# Sheet1.net
KiCad netlist of a schematic drawn in Altium Designer
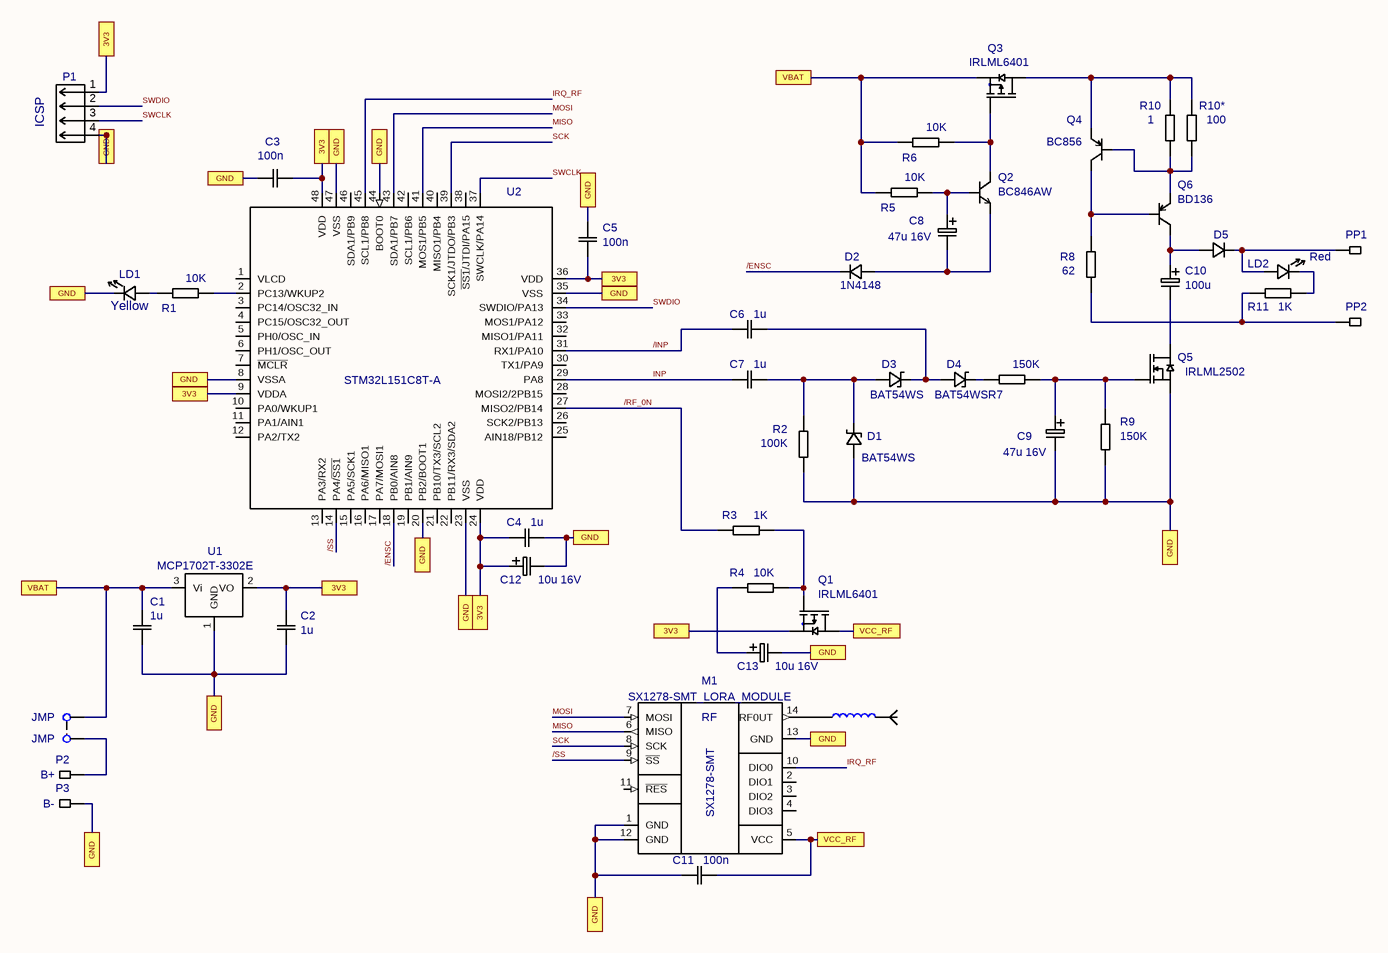
[diagram p0: Sheet1.SCHDOC]

(export (version "E")
  (design (tool "Eeschema 10.0.6"))
  (components
    (comp (ref "C1")
      (value "1u")
      (footprint "C0805")
      (description "CAP_SMD_0805")
      (libsource (lib "*") (part "CAP_SMD_0805"))
    )
    (comp (ref "C2")
      (value "1u")
      (footprint "C0805")
      (description "CAP_SMD_0805")
      (libsource (lib "*") (part "CAP_SMD_0805"))
    )
    (comp (ref "C3")
      (value "100n")
      (footprint "C0805")
      (description "CAP_SMD_0805")
      (libsource (lib "") (part "CAP_SMD_0805_2"))
    )
    (comp (ref "C4")
      (value "1u")
      (footprint "C0805")
      (description "CAP_SMD_0805")
      (libsource (lib "") (part "CAP_SMD_0805_2"))
    )
    (comp (ref "C5")
      (value "100n")
      (footprint "C0805")
      (description "CAP_SMD_0805")
      (libsource (lib "*") (part "CAP_SMD_0805"))
    )
    (comp (ref "C6")
      (value "1u")
      (footprint "C0805")
      (description "CAP_SMD_0805")
      (libsource (lib "") (part "CAP_SMD_0805_2"))
    )
    (comp (ref "C7")
      (value "1u")
      (footprint "C0805")
      (description "CAP_SMD_0805")
      (libsource (lib "") (part "CAP_SMD_0805_1"))
    )
    (comp (ref "C8")
      (value "47u 16V")
      (footprint "ECAP-SD-D5L11")
      (description "ECAP-RD-D5L11")
      (libsource (lib "*") (part "ECAP-RD-D5L11"))
    )
    (comp (ref "C9")
      (value "47u 16V")
      (footprint "ECAP-SD-D5L11")
      (description "ECAP-RD-D5L11")
      (libsource (lib "*") (part "ECAP-RD-D5L11"))
    )
    (comp (ref "C10")
      (value "100u")
      (footprint "ECAP-SD-D6.3L11")
      (description "ECAP-RD-D6.3L11")
      (libsource (lib "*") (part "ECAP-RD-D6.3L11"))
    )
    (comp (ref "C11")
      (value "100n")
      (footprint "C0805")
      (description "CAP_SMD_0805")
      (libsource (lib "") (part "CAP_SMD_0805_1"))
    )
    (comp (ref "C12")
      (value "10u 16V")
      (footprint "ECAP-SD-D5L11")
      (description "ECAP-RD-D5L11")
      (libsource (lib "*") (part "ECAP-RD-D5L11"))
    )
    (comp (ref "C13")
      (value "10u 16V")
      (footprint "ECAP-SD-D5L11")
      (description "ECAP-RD-D5L11")
      (libsource (lib "*") (part "ECAP-RD-D5L11"))
    )
    (comp (ref "D1") (value "BAT54WS") (footprint "SOD323") (libsource (lib "*") (part "BAT54WS")))
    (comp (ref "D2") (value "1N4148") (footprint "SOD80") (libsource (lib "*") (part "1N4148")))
    (comp (ref "D3") (value "BAT54WS") (footprint "SOD323") (libsource (lib "*") (part "BAT54WS")))
    (comp (ref "D4") (value "BAT54WS") (footprint "SOD323") (libsource (lib "*") (part "BAT54WS")))
    (comp (ref "D5") (value "1N4007-A7") (footprint "SOD-123FL") (libsource (lib "*") (part "1N4007-A7")))
    (comp (ref "LD1")
      (value "Yellow")
      (footprint "LED_SMD_0805")
      (description "Yellow LED. 2.6Vf")
      (fields (field (name "Comment") "FYLS-0805BYC LED"))
      (libsource (lib "*") (part "FYLS-0805BYC LED"))
    )
    (comp (ref "LD2")
      (value "Red")
      (footprint "LED_SMD_0805")
      (description "Ultra Red. Vf-1.85V(2.2V max)")
      (fields (field (name "Comment") "FYLS-0805URC LED"))
      (libsource (lib "*") (part "FYLS-0805URC LED"))
    )
    (comp (ref "M1")
      (value "SX1278-SMT_LORA_MODULE")
      (footprint "SX1278-SMT_MODULE")
      (libsource (lib "*") (part "SX1278-SMT_LORA_MODULE"))
    )
    (comp (ref "P1")
      (value "ICSP")
      (footprint "PLS-04SMD")
      (description "PLS-04SMD")
      (libsource (lib "*") (part "PLS-04SMD"))
    )
    (comp (ref "P2")
      (value "B+")
      (footprint "PAD_RRX60Y120D0T")
      (description "PAD_RRX60Y120D0T")
      (libsource (lib "*") (part "PAD_RRX60Y120D0T"))
    )
    (comp (ref "P3")
      (value "B-")
      (footprint "PAD_RRX60Y120D0T")
      (description "PAD_RRX60Y120D0T")
      (libsource (lib "*") (part "PAD_RRX60Y120D0T"))
    )
    (comp (ref "PP1")
      (value "PAD_RRX60Y120D0T")
      (footprint "PAD_RRX60Y120D0T")
      (libsource (lib "*") (part "PAD_RRX60Y120D0T"))
    )
    (comp (ref "PP2")
      (value "PAD_RRX60Y120D0T")
      (footprint "PAD_RRX60Y120D0T")
      (libsource (lib "*") (part "PAD_RRX60Y120D0T"))
    )
    (comp (ref "PP3")
      (value "JMP")
      (footprint "PAD_RX60Y60D38A")
      (description "PAD_RX60Y60D38A")
      (libsource (lib "*") (part "PAD_RX60Y60D38A"))
    )
    (comp (ref "PP4")
      (value "JMP")
      (footprint "PAD_RX60Y60D38A")
      (description "PAD_RX60Y60D38A")
      (libsource (lib "*") (part "PAD_RX60Y60D38A"))
    )
    (comp (ref "Q1") (value "IRLML6401") (footprint "SOT23") (libsource (lib "*") (part "IRLML6401")))
    (comp (ref "Q2") (value "BC846AW") (footprint "SOT23") (libsource (lib "*") (part "BC846AW")))
    (comp (ref "Q3") (value "IRLML6401") (footprint "SOT23") (libsource (lib "") (part "IRLML6401_1")))
    (comp (ref "Q4") (value "BC856") (footprint "SOT23") (libsource (lib "*") (part "BC856")))
    (comp (ref "Q5") (value "IRLML2502") (footprint "SOT23") (libsource (lib "*") (part "IRLML2502")))
    (comp (ref "Q6") (value "BD136") (footprint "TO225 VH") (libsource (lib "*") (part "BD136")))
    (comp (ref "R1")
      (value "10K")
      (footprint "R0805")
      (description "RES_SMD_0805")
      (libsource (lib "*") (part "RES_SMD_0805"))
    )
    (comp (ref "R2")
      (value "100K")
      (footprint "R0805")
      (description "RES_SMD_0805")
      (libsource (lib "*") (part "RES_SMD_0805"))
    )
    (comp (ref "R3")
      (value "1K")
      (footprint "R0805")
      (description "RES_SMD_0805")
      (libsource (lib "*") (part "RES_SMD_0805"))
    )
    (comp (ref "R4")
      (value "10K")
      (footprint "R0805")
      (description "RES_SMD_0805")
      (libsource (lib "*") (part "RES_SMD_0805"))
    )
    (comp (ref "R5")
      (value "10K")
      (footprint "R0805")
      (description "RES_SMD_0805")
      (libsource (lib "*") (part "RES_SMD_0805"))
    )
    (comp (ref "R6")
      (value "10K")
      (footprint "R0805")
      (description "RES_SMD_0805")
      (libsource (lib "*") (part "RES_SMD_0805"))
    )
    (comp (ref "R7")
      (value "150K")
      (footprint "R0805")
      (description "RES_SMD_0805")
      (libsource (lib "*") (part "RES_SMD_0805"))
    )
    (comp (ref "R8")
      (value "62")
      (footprint "R0805")
      (description "RES_SMD_0805")
      (libsource (lib "*") (part "RES_SMD_0805"))
    )
    (comp (ref "R9")
      (value "150K")
      (footprint "R0805")
      (description "RES_SMD_0805")
      (libsource (lib "*") (part "RES_SMD_0805"))
    )
    (comp (ref "R10")
      (value "1")
      (footprint "R0805")
      (description "RES_SMD_0805")
      (libsource (lib "*") (part "RES_SMD_0805"))
    )
    (comp (ref "R10*")
      (value "100")
      (footprint "R0805")
      (description "RES_SMD_0805")
      (libsource (lib "*") (part "RES_SMD_0805"))
    )
    (comp (ref "R11")
      (value "1K")
      (footprint "R0805")
      (description "RES_SMD_0805")
      (libsource (lib "*") (part "RES_SMD_0805"))
    )
    (comp (ref "U1")
      (value "MCP1702T-3302E")
      (footprint "SOT23A")
      (libsource (lib "*") (part "MCP1702T-3302E"))
    )
    (comp (ref "U2")
      (value "STM32L151C8T-A")
      (footprint "LQFP48 7X7")
      (libsource (lib "*") (part "STM32L151C8T-A"))
    )
  )
  (nets
    (net (code "1") (name "/3V3") (class "Default")
      (node (ref "C12") (pin "1") (pintype "passive"))
      (node (ref "C2") (pin "2") (pinfunction "B_2") (pintype "passive"))
      (node (ref "C3") (pin "1") (pinfunction "A_1") (pintype "passive"))
      (node (ref "C4") (pin "2") (pinfunction "B_2") (pintype "passive"))
      (node (ref "C5") (pin "1") (pinfunction "A_1") (pintype "passive"))
      (node (ref "P1") (pin "1") (pintype "passive"))
      (node (ref "Q1") (pin "2") (pinfunction "S_2") (pintype "passive"))
      (node (ref "U1") (pin "2") (pinfunction "VO_2") (pintype "passive"))
      (node (ref "U2") (pin "24") (pinfunction "VDD_24") (pintype "power_in"))
      (node (ref "U2") (pin "36") (pinfunction "VDD_36") (pintype "power_in"))
      (node (ref "U2") (pin "48") (pinfunction "VDD_48") (pintype "power_in"))
      (node (ref "U2") (pin "9") (pinfunction "VDDA_9") (pintype "power_in"))
    )
    (net (code "2") (name "/GND") (class "Default")
      (node (ref "C1") (pin "1") (pinfunction "A_1") (pintype "passive"))
      (node (ref "C11") (pin "1") (pinfunction "A_1") (pintype "passive"))
      (node (ref "C12") (pin "2") (pintype "passive"))
      (node (ref "C13") (pin "2") (pintype "passive"))
      (node (ref "C2") (pin "1") (pinfunction "A_1") (pintype "passive"))
      (node (ref "C3") (pin "2") (pinfunction "B_2") (pintype "passive"))
      (node (ref "C4") (pin "1") (pinfunction "A_1") (pintype "passive"))
      (node (ref "C5") (pin "2") (pinfunction "B_2") (pintype "passive"))
      (node (ref "C9") (pin "2") (pintype "passive"))
      (node (ref "D1") (pin "1") (pintype "passive"))
      (node (ref "LD1") (pin "K") (pinfunction "K_K") (pintype "passive"))
      (node (ref "M1") (pin "1") (pinfunction "GND_1") (pintype "power_in"))
      (node (ref "M1") (pin "12") (pinfunction "GND_12") (pintype "power_in"))
      (node (ref "M1") (pin "13") (pinfunction "GND_13") (pintype "power_in"))
      (node (ref "P1") (pin "4") (pintype "passive"))
      (node (ref "P3") (pin "1") (pintype "passive"))
      (node (ref "Q5") (pin "2") (pinfunction "S_2") (pintype "passive"))
      (node (ref "R2") (pin "2") (pintype "passive"))
      (node (ref "R9") (pin "2") (pintype "passive"))
      (node (ref "U1") (pin "1") (pinfunction "GND_1") (pintype "passive"))
      (node (ref "U2") (pin "20") (pinfunction "PB2/BOOT1_20") (pintype "bidirectional"))
      (node (ref "U2") (pin "23") (pinfunction "VSS_23") (pintype "power_in"))
      (node (ref "U2") (pin "35") (pinfunction "VSS_35") (pintype "power_in"))
      (node (ref "U2") (pin "44") (pinfunction "BOOT0_44") (pintype "input"))
      (node (ref "U2") (pin "47") (pinfunction "VSS_47") (pintype "power_in"))
      (node (ref "U2") (pin "8") (pinfunction "VSSA_8") (pintype "power_in"))
    )
    (net (code "3") (name "/INP") (class "Default")
      (node (ref "C7") (pin "1") (pinfunction "A_1") (pintype "passive"))
      (node (ref "U2") (pin "29") (pinfunction "PA8_29") (pintype "bidirectional"))
    )
    (net (code "4") (name "/IRQ_RF") (class "Default")
      (node (ref "M1") (pin "10") (pinfunction "DIO0_10") (pintype "bidirectional"))
      (node (ref "U2") (pin "45") (pinfunction "SCL1/PB8_45") (pintype "bidirectional"))
    )
    (net (code "5") (name "/MISO") (class "Default")
      (node (ref "M1") (pin "6") (pinfunction "MISO_6") (pintype "output"))
      (node (ref "U2") (pin "41") (pinfunction "MOS1/PB5_41") (pintype "bidirectional"))
    )
    (net (code "6") (name "/MOSI") (class "Default")
      (node (ref "M1") (pin "7") (pinfunction "MOSI_7") (pintype "input"))
      (node (ref "U2") (pin "43") (pinfunction "SDA1/PB7_43") (pintype "bidirectional"))
    )
    (net (code "7") (name "/SCK") (class "Default")
      (node (ref "M1") (pin "8") (pinfunction "SCK_8") (pintype "input"))
      (node (ref "U2") (pin "39") (pinfunction "SCK1/JTDO/PB3_39") (pintype "bidirectional"))
    )
    (net (code "8") (name "/SWCLK") (class "Default")
      (node (ref "P1") (pin "3") (pintype "passive"))
      (node (ref "U2") (pin "37") (pinfunction "SWCLK/PA14_37") (pintype "bidirectional"))
    )
    (net (code "9") (name "/SWDIO") (class "Default")
      (node (ref "P1") (pin "2") (pintype "passive"))
      (node (ref "U2") (pin "34") (pinfunction "SWDIO/PA13_34") (pintype "bidirectional"))
    )
    (net (code "10") (name "/VBAT") (class "Default")
      (node (ref "C1") (pin "2") (pinfunction "B_2") (pintype "passive"))
      (node (ref "PP4") (pin "1") (pintype "passive"))
      (node (ref "Q3") (pin "2") (pinfunction "S_2") (pintype "passive"))
      (node (ref "R5") (pin "2") (pintype "passive"))
      (node (ref "R6") (pin "2") (pintype "passive"))
      (node (ref "U1") (pin "3") (pinfunction "Vi_3") (pintype "passive"))
    )
    (net (code "11") (name "/VCC_RF") (class "Default")
      (node (ref "C11") (pin "2") (pinfunction "B_2") (pintype "passive"))
      (node (ref "M1") (pin "5") (pinfunction "VCC_5") (pintype "power_in"))
      (node (ref "Q1") (pin "3") (pinfunction "D_3") (pintype "passive"))
    )
    (net (code "12") (name "/{slash}ENSC") (class "Default")
      (node (ref "D2") (pin "K") (pinfunction "K_K") (pintype "passive"))
      (node (ref "U2") (pin "18") (pinfunction "PB0/AIN8_18") (pintype "bidirectional"))
    )
    (net (code "13") (name "/{slash}INP") (class "Default")
      (node (ref "C6") (pin "2") (pinfunction "B_2") (pintype "passive"))
      (node (ref "U2") (pin "31") (pinfunction "RX1/PA10_31") (pintype "bidirectional"))
    )
    (net (code "14") (name "/{slash}RF_0N") (class "Default")
      (node (ref "R3") (pin "2") (pintype "passive"))
      (node (ref "U2") (pin "27") (pinfunction "MISO2/PB14_27") (pintype "bidirectional"))
    )
    (net (code "15") (name "/{slash}SS") (class "Default")
      (node (ref "M1") (pin "9") (pinfunction "~{SS}_9") (pintype "input"))
      (node (ref "U2") (pin "14") (pinfunction "PA4/~{SS1}_14") (pintype "bidirectional"))
    )
    (net (code "16") (name "Net-(C6-A)") (class "Default")
      (node (ref "C6") (pin "1") (pinfunction "A_1") (pintype "passive"))
      (node (ref "D3") (pin "2") (pintype "passive"))
      (node (ref "D4") (pin "1") (pintype "passive"))
    )
    (net (code "17") (name "Net-(C7-B)") (class "Default")
      (node (ref "C7") (pin "2") (pinfunction "B_2") (pintype "passive"))
      (node (ref "D1") (pin "2") (pintype "passive"))
      (node (ref "D3") (pin "1") (pintype "passive"))
      (node (ref "R2") (pin "1") (pintype "passive"))
    )
    (net (code "18") (name "Net-(C13-Pad1)") (class "Default")
      (node (ref "C13") (pin "1") (pintype "passive"))
      (node (ref "R4") (pin "2") (pintype "passive"))
    )
    (net (code "19") (name "Net-(D4-Pad2)") (class "Default")
      (node (ref "D4") (pin "2") (pintype "passive"))
      (node (ref "R7") (pin "2") (pintype "passive"))
    )
    (net (code "20") (name "Net-(D5-A)") (class "Default")
      (node (ref "C10") (pin "1") (pintype "passive"))
      (node (ref "D5") (pin "1") (pinfunction "A_1") (pintype "passive"))
      (node (ref "Q6") (pin "2") (pinfunction "K_2") (pintype "passive"))
    )
    (net (code "21") (name "Net-(D5-K)") (class "Default")
      (node (ref "D5") (pin "2") (pinfunction "K_2") (pintype "passive"))
      (node (ref "LD2") (pin "A") (pinfunction "A_A") (pintype "passive"))
      (node (ref "PP1") (pin "1") (pintype "passive"))
    )
    (net (code "22") (name "Net-(LD1-PadA)") (class "Default")
      (node (ref "LD1") (pin "A") (pinfunction "A_A") (pintype "passive"))
      (node (ref "R1") (pin "2") (pintype "passive"))
    )
    (net (code "23") (name "Net-(LD2-PadK)") (class "Default")
      (node (ref "LD2") (pin "K") (pinfunction "K_K") (pintype "passive"))
      (node (ref "R11") (pin "1") (pintype "passive"))
    )
    (net (code "24") (name "Net-(P2-Pad1)") (class "Default")
      (node (ref "P2") (pin "1") (pintype "passive"))
      (node (ref "PP3") (pin "1") (pintype "passive"))
    )
    (net (code "25") (name "Net-(PP2-Pad1)") (class "Default")
      (node (ref "PP2") (pin "1") (pintype "passive"))
      (node (ref "R11") (pin "2") (pintype "passive"))
      (node (ref "R8") (pin "2") (pintype "passive"))
    )
    (net (code "26") (name "Net-(Q1-G)") (class "Default")
      (node (ref "Q1") (pin "1") (pinfunction "G_1") (pintype "passive"))
      (node (ref "R3") (pin "1") (pintype "passive"))
      (node (ref "R4") (pin "1") (pintype "passive"))
    )
    (net (code "27") (name "Net-(Q2-B)") (class "Default")
      (node (ref "C8") (pin "1") (pintype "passive"))
      (node (ref "Q2") (pin "1") (pinfunction "B_1") (pintype "passive"))
      (node (ref "R5") (pin "1") (pintype "passive"))
    )
    (net (code "28") (name "Net-(Q2-C)") (class "Default")
      (node (ref "Q2") (pin "3") (pinfunction "C_3") (pintype "passive"))
      (node (ref "Q3") (pin "1") (pinfunction "G_1") (pintype "passive"))
      (node (ref "R6") (pin "1") (pintype "passive"))
    )
    (net (code "29") (name "Net-(Q2-E)") (class "Default")
      (node (ref "C8") (pin "2") (pintype "passive"))
      (node (ref "D2") (pin "A") (pinfunction "A_A") (pintype "passive"))
      (node (ref "Q2") (pin "2") (pinfunction "E_2") (pintype "passive"))
    )
    (net (code "30") (name "Net-(Q3-D)") (class "Default")
      (node (ref "Q3") (pin "3") (pinfunction "D_3") (pintype "passive"))
      (node (ref "Q4") (pin "2") (pinfunction "E_2") (pintype "passive"))
      (node (ref "R10") (pin "1") (pintype "passive"))
      (node (ref "R10*") (pin "1") (pintype "passive"))
    )
    (net (code "31") (name "Net-(Q4-B)") (class "Default")
      (node (ref "Q4") (pin "1") (pinfunction "B_1") (pintype "passive"))
      (node (ref "Q6") (pin "1") (pinfunction "E_1") (pintype "passive"))
      (node (ref "R10") (pin "2") (pintype "passive"))
      (node (ref "R10*") (pin "2") (pintype "passive"))
    )
    (net (code "32") (name "Net-(Q4-C)") (class "Default")
      (node (ref "Q4") (pin "3") (pinfunction "C_3") (pintype "passive"))
      (node (ref "Q6") (pin "3") (pinfunction "B_3") (pintype "passive"))
      (node (ref "R8") (pin "1") (pintype "passive"))
    )
    (net (code "33") (name "Net-(Q5-D)") (class "Default")
      (node (ref "C10") (pin "2") (pintype "passive"))
      (node (ref "Q5") (pin "3") (pinfunction "D_3") (pintype "passive"))
    )
    (net (code "34") (name "Net-(Q5-G)") (class "Default")
      (node (ref "C9") (pin "1") (pintype "passive"))
      (node (ref "Q5") (pin "1") (pinfunction "G_1") (pintype "passive"))
      (node (ref "R7") (pin "1") (pintype "passive"))
      (node (ref "R9") (pin "1") (pintype "passive"))
    )
    (net (code "35") (name "Net-(U2-PC13{slash}WKUP2)") (class "Default")
      (node (ref "R1") (pin "1") (pintype "passive"))
      (node (ref "U2") (pin "2") (pinfunction "PC13/WKUP2_2") (pintype "bidirectional"))
    )
    (net (code "36") (name "unconnected-(M1-DIO1-Pad2)") (class "Default")
      (node (ref "M1") (pin "2") (pinfunction "DIO1_2") (pintype "bidirectional"))
    )
    (net (code "37") (name "unconnected-(M1-DIO2-Pad3)") (class "Default")
      (node (ref "M1") (pin "3") (pinfunction "DIO2_3") (pintype "bidirectional"))
    )
    (net (code "38") (name "unconnected-(M1-DIO3-Pad4)") (class "Default")
      (node (ref "M1") (pin "4") (pinfunction "DIO3_4") (pintype "bidirectional"))
    )
    (net (code "39") (name "unconnected-(M1-RF0UT-Pad14)") (class "Default")
      (node (ref "M1") (pin "14") (pinfunction "RF0UT_14") (pintype "output"))
    )
    (net (code "40") (name "unconnected-(M1-~{RES}-Pad11)") (class "Default")
      (node (ref "M1") (pin "11") (pinfunction "~{RES}_11") (pintype "input"))
    )
    (net (code "41") (name "unconnected-(U2-AIN18{slash}PB12-Pad25)") (class "Default")
      (node (ref "U2") (pin "25") (pinfunction "AIN18/PB12_25") (pintype "bidirectional"))
    )
    (net (code "42") (name "unconnected-(U2-MISO1{slash}PA11-Pad32)") (class "Default")
      (node (ref "U2") (pin "32") (pinfunction "MISO1/PA11_32") (pintype "bidirectional"))
    )
    (net (code "43") (name "unconnected-(U2-MISO1{slash}PB4-Pad40)") (class "Default")
      (node (ref "U2") (pin "40") (pinfunction "MISO1/PB4_40") (pintype "bidirectional"))
    )
    (net (code "44") (name "unconnected-(U2-MOS1{slash}PA12-Pad33)") (class "Default")
      (node (ref "U2") (pin "33") (pinfunction "MOS1/PA12_33") (pintype "bidirectional"))
    )
    (net (code "45") (name "unconnected-(U2-MOSI2{slash}2PB15-Pad28)") (class "Default")
      (node (ref "U2") (pin "28") (pinfunction "MOSI2/2PB15_28") (pintype "bidirectional"))
    )
    (net (code "46") (name "unconnected-(U2-PA0{slash}WKUP1-Pad10)") (class "Default")
      (node (ref "U2") (pin "10") (pinfunction "PA0/WKUP1_10") (pintype "bidirectional"))
    )
    (net (code "47") (name "unconnected-(U2-PA1{slash}AIN1-Pad11)") (class "Default")
      (node (ref "U2") (pin "11") (pinfunction "PA1/AIN1_11") (pintype "bidirectional"))
    )
    (net (code "48") (name "unconnected-(U2-PA2{slash}TX2-Pad12)") (class "Default")
      (node (ref "U2") (pin "12") (pinfunction "PA2/TX2_12") (pintype "bidirectional"))
    )
    (net (code "49") (name "unconnected-(U2-PA3{slash}RX2-Pad13)") (class "Default")
      (node (ref "U2") (pin "13") (pinfunction "PA3/RX2_13") (pintype "bidirectional"))
    )
    (net (code "50") (name "unconnected-(U2-PA5{slash}SCK1-Pad15)") (class "Default")
      (node (ref "U2") (pin "15") (pinfunction "PA5/SCK1_15") (pintype "bidirectional"))
    )
    (net (code "51") (name "unconnected-(U2-PA6{slash}MISO1-Pad16)") (class "Default")
      (node (ref "U2") (pin "16") (pinfunction "PA6/MISO1_16") (pintype "bidirectional"))
    )
    (net (code "52") (name "unconnected-(U2-PA7{slash}MOSI1-Pad17)") (class "Default")
      (node (ref "U2") (pin "17") (pinfunction "PA7/MOSI1_17") (pintype "bidirectional"))
    )
    (net (code "53") (name "unconnected-(U2-PB1{slash}AIN9-Pad19)") (class "Default")
      (node (ref "U2") (pin "19") (pinfunction "PB1/AIN9_19") (pintype "bidirectional"))
    )
    (net (code "54") (name "unconnected-(U2-PB10{slash}TX3{slash}SCL2-Pad21)") (class "Default")
      (node (ref "U2") (pin "21") (pinfunction "PB10/TX3/SCL2_21") (pintype "bidirectional"))
    )
    (net (code "55") (name "unconnected-(U2-PB11{slash}RX3{slash}SDA2-Pad22)") (class "Default")
      (node (ref "U2") (pin "22") (pinfunction "PB11/RX3/SDA2_22") (pintype "bidirectional"))
    )
    (net (code "56") (name "unconnected-(U2-PC14{slash}OSC32_IN-Pad3)") (class "Default")
      (node (ref "U2") (pin "3") (pinfunction "PC14/OSC32_IN_3") (pintype "bidirectional"))
    )
    (net (code "57") (name "unconnected-(U2-PC15{slash}OSC32_OUT-Pad4)") (class "Default")
      (node (ref "U2") (pin "4") (pinfunction "PC15/OSC32_OUT_4") (pintype "bidirectional"))
    )
    (net (code "58") (name "unconnected-(U2-PH0{slash}OSC_IN-Pad5)") (class "Default")
      (node (ref "U2") (pin "5") (pinfunction "PH0/OSC_IN_5") (pintype "bidirectional"))
    )
    (net (code "59") (name "unconnected-(U2-PH1{slash}OSC_OUT-Pad6)") (class "Default")
      (node (ref "U2") (pin "6") (pinfunction "PH1/OSC_OUT_6") (pintype "bidirectional"))
    )
    (net (code "60") (name "unconnected-(U2-SCK2{slash}PB13-Pad26)") (class "Default")
      (node (ref "U2") (pin "26") (pinfunction "SCK2/PB13_26") (pintype "bidirectional"))
    )
    (net (code "61") (name "unconnected-(U2-SCL1{slash}PB6-Pad42)") (class "Default")
      (node (ref "U2") (pin "42") (pinfunction "SCL1/PB6_42") (pintype "bidirectional"))
    )
    (net (code "62") (name "unconnected-(U2-SDA1{slash}PB9-Pad46)") (class "Default")
      (node (ref "U2") (pin "46") (pinfunction "SDA1/PB9_46") (pintype "bidirectional"))
    )
    (net (code "63") (name "unconnected-(U2-TX1{slash}PA9-Pad30)") (class "Default")
      (node (ref "U2") (pin "30") (pinfunction "TX1/PA9_30") (pintype "bidirectional"))
    )
    (net (code "64") (name "unconnected-(U2-VLCD-Pad1)") (class "Default")
      (node (ref "U2") (pin "1") (pinfunction "VLCD_1") (pintype "power_in"))
    )
    (net (code "65") (name "unconnected-(U2-~{MCLR}-Pad7)") (class "Default")
      (node (ref "U2") (pin "7") (pinfunction "~{MCLR}_7") (pintype "bidirectional"))
    )
    (net (code "66") (name "unconnected-(U2-~{SS1}{slash}JTDI{slash}PA15-Pad38)") (class "Default")
      (node (ref "U2") (pin "38") (pinfunction "~{SS1}/JTDI/PA15_38") (pintype "bidirectional"))
    )
  )
)
